# MINI_SAM_D51_r025_b001.net
KiCad netlist of a schematic drawn in EAGLE
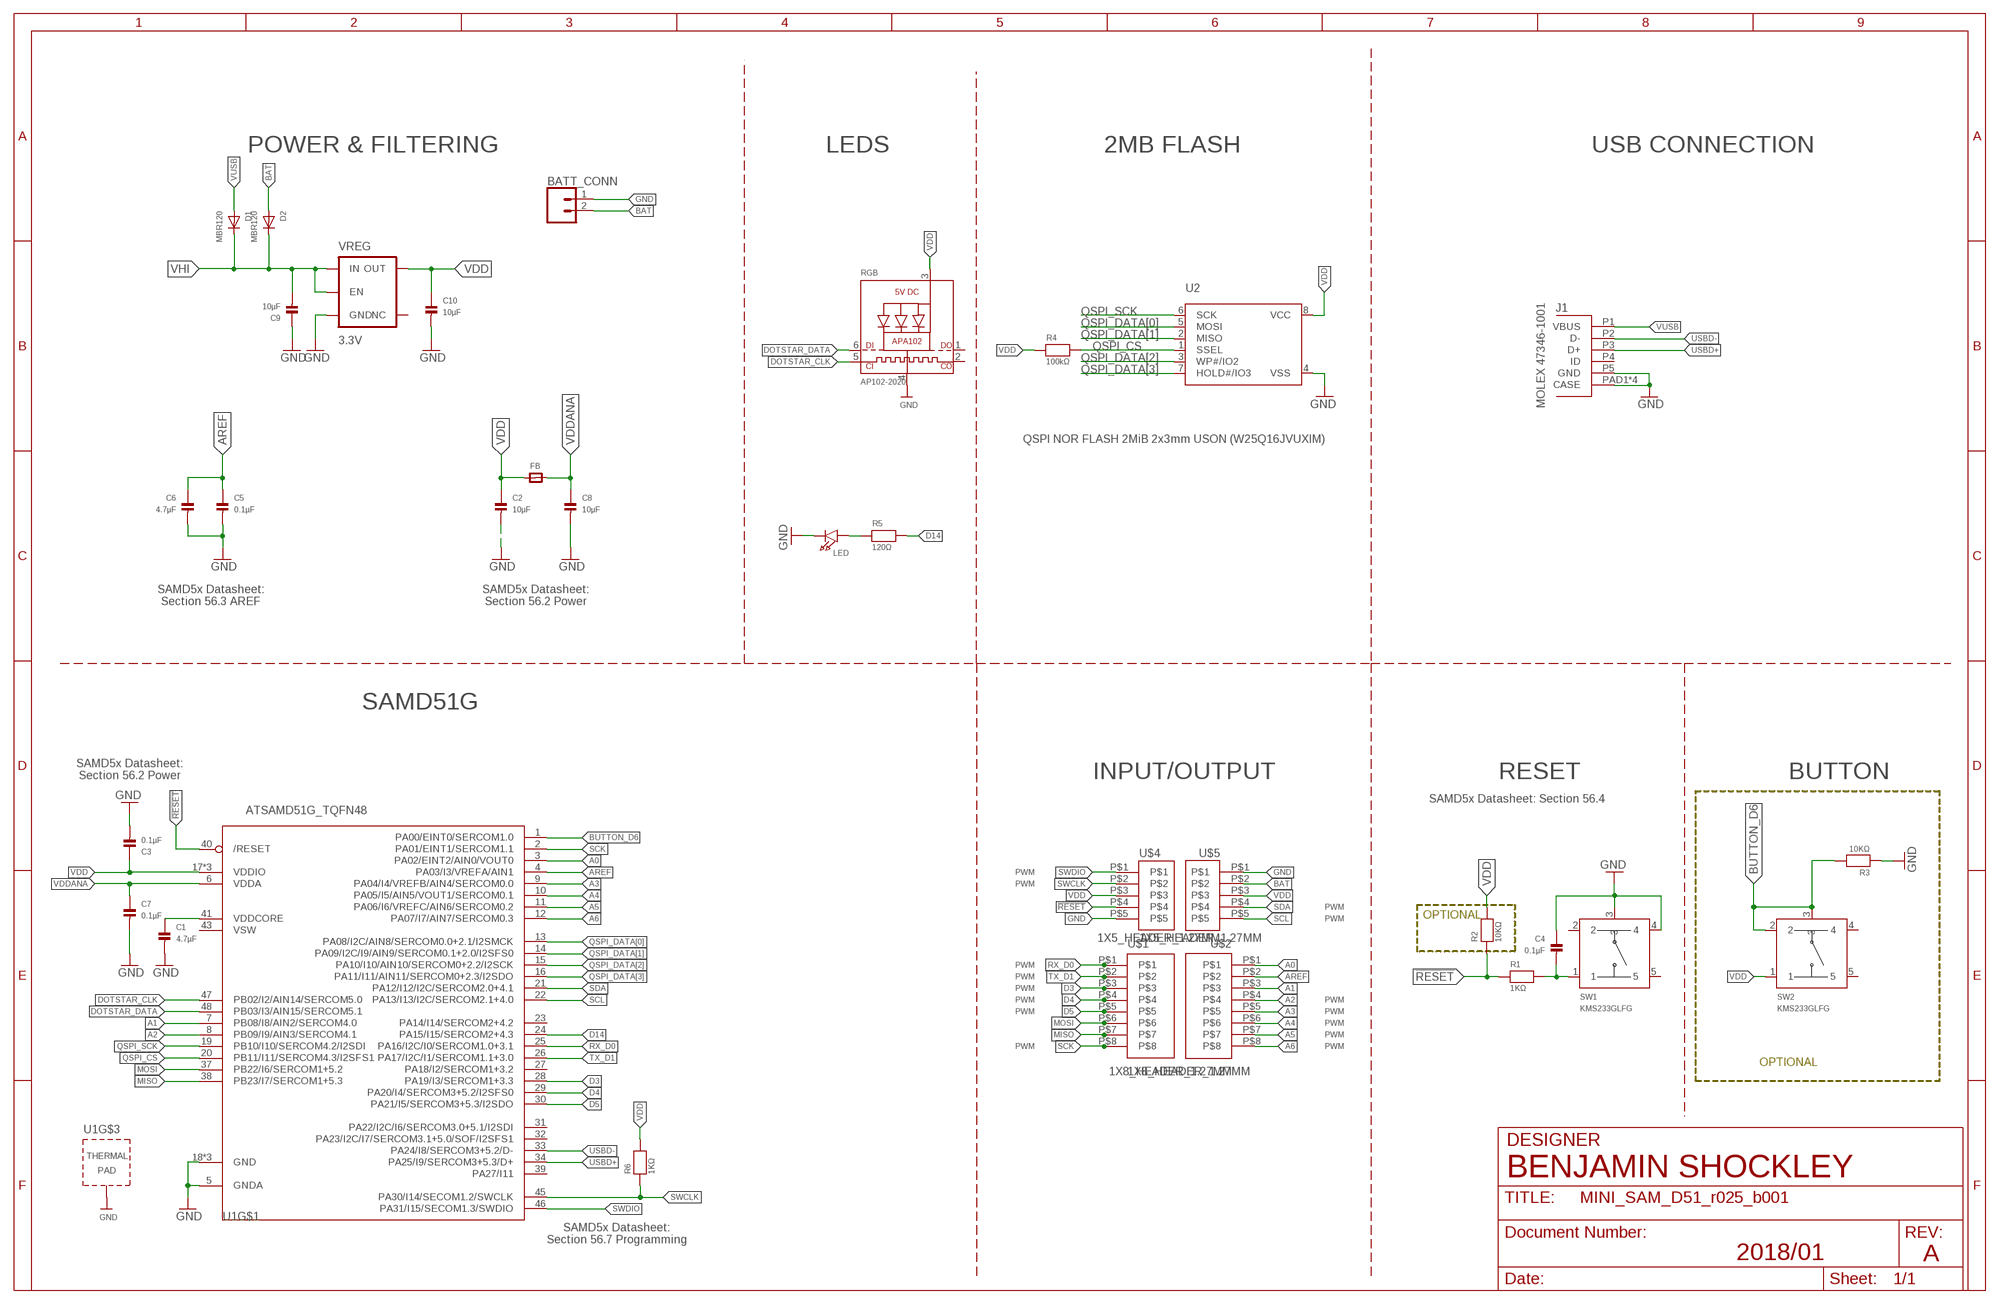
[diagram p0: schematic, sheet 1]

(export (version "E")
  (design (tool "Eeschema 10.0.6"))
  (components
    (comp (ref "BATT_CONN")
      (value "CONN_02-JST-2MM-SMT")
      (footprint "eagle-import:JST-2-SMD_NO_PASTE")
      (libsource (lib "eagle-import") (part "CONN_02-JST-2MM-SMT"))
    )
    (comp (ref "C1")
      (value "4.7µF")
      (footprint "eagle-import:0603_CAPACITOR")
      (libsource (lib "eagle-import") (part "CAP_CERAMICQUIRKY"))
    )
    (comp (ref "C2")
      (value "10µF")
      (footprint "eagle-import:0603_CAPACITOR")
      (libsource (lib "eagle-import") (part "CAP_CERAMICQUIRKY"))
    )
    (comp (ref "C3")
      (value "0.1µF")
      (footprint "eagle-import:0603_CAPACITOR")
      (libsource (lib "eagle-import") (part "CAP_CERAMICQUIRKY"))
    )
    (comp (ref "C4")
      (value "0.1µF")
      (footprint "eagle-import:0603_CAPACITOR")
      (libsource (lib "eagle-import") (part "CAP_CERAMICQUIRKY"))
    )
    (comp (ref "C5")
      (value "0.1µF")
      (footprint "eagle-import:0603_CAPACITOR")
      (libsource (lib "eagle-import") (part "CAP_CERAMICQUIRKY"))
    )
    (comp (ref "C6")
      (value "4.7µF")
      (footprint "eagle-import:0603_CAPACITOR")
      (libsource (lib "eagle-import") (part "CAP_CERAMICQUIRKY"))
    )
    (comp (ref "C7")
      (value "0.1µF")
      (footprint "eagle-import:0603_CAPACITOR")
      (libsource (lib "eagle-import") (part "CAP_CERAMICQUIRKY"))
    )
    (comp (ref "C8")
      (value "10µF")
      (footprint "eagle-import:0603_CAPACITOR")
      (libsource (lib "eagle-import") (part "CAP_CERAMICQUIRKY"))
    )
    (comp (ref "C9")
      (value "10µF")
      (footprint "eagle-import:0603_CAPACITOR")
      (libsource (lib "eagle-import") (part "CAP_CERAMICQUIRKY"))
    )
    (comp (ref "C10")
      (value "10µF")
      (footprint "eagle-import:0603_CAPACITOR")
      (libsource (lib "eagle-import") (part "CAP_CERAMICQUIRKY"))
    )
    (comp (ref "D1")
      (value "MBR120")
      (footprint "eagle-import:SOD-123FL")
      (libsource (lib "eagle-import") (part "DIODE_SOD-123FL"))
    )
    (comp (ref "D2")
      (value "MBR120")
      (footprint "eagle-import:SOD-123FL")
      (libsource (lib "eagle-import") (part "DIODE_SOD-123FL"))
    )
    (comp (ref "FB")
      (value "Impedence: 50 ohm @ 20 MHz, 220 Ohm @ 100 MHz; low DC resistance")
      (footprint "eagle-import:0603_INDUCTOR")
      (libsource (lib "eagle-import") (part "FERRITEQUIRKY"))
    )
    (comp (ref "J1")
      (value "MOLEX_47346-100147346")
      (footprint "eagle-import:MOLEX_47346-1001")
      (libsource (lib "eagle-import") (part "MOLEX_47346-100147346"))
    )
    (comp (ref "LED")
      (value "VLRK31Q1R2-GS08")
      (footprint "eagle-import:REVERSE_MOUNT_LED")
      (libsource (lib "eagle-import") (part "REVERSEMOUNTLED"))
    )
    (comp (ref "R1")
      (value "1KΩ")
      (footprint "eagle-import:0603_RESISTOR")
      (libsource (lib "eagle-import") (part "RESISTORQUIRKY"))
    )
    (comp (ref "R2")
      (value "10KΩ")
      (footprint "eagle-import:0603_RESISTOR")
      (libsource (lib "eagle-import") (part "RESISTORQUIRKY"))
    )
    (comp (ref "R3")
      (value "10KΩ")
      (footprint "eagle-import:0603_RESISTOR")
      (libsource (lib "eagle-import") (part "RESISTORQUIRKY"))
    )
    (comp (ref "R4")
      (value "100kΩ")
      (footprint "eagle-import:0603_RESISTOR")
      (libsource (lib "eagle-import") (part "RESISTORQUIRKY"))
    )
    (comp (ref "R5")
      (value "120Ω")
      (footprint "eagle-import:0603_RESISTOR")
      (libsource (lib "eagle-import") (part "RESISTORQUIRKY"))
    )
    (comp (ref "R6")
      (value "1KΩ")
      (footprint "eagle-import:0603_RESISTOR")
      (libsource (lib "eagle-import") (part "RESISTORQUIRKY"))
    )
    (comp (ref "RGB")
      (value "AP102-2020")
      (footprint "eagle-import:APA102_2020")
      (libsource (lib "eagle-import") (part "APA1022020"))
    )
    (comp (ref "SW1")
      (value "KMS233GLFG")
      (footprint "eagle-import:KMS_SWITCH")
      (libsource (lib "eagle-import") (part "KMS_SWITCHKMS"))
    )
    (comp (ref "SW2")
      (value "KMS233GLFG")
      (footprint "eagle-import:KMS_SWITCH")
      (libsource (lib "eagle-import") (part "KMS_SWITCHKMS"))
    )
    (comp (ref "U$1")
      (value "1X8_HEADER_1.27MM")
      (footprint "eagle-import:1X8_HEADER_1.27MM")
      (libsource (lib "eagle-import") (part "1X8_HEADER_1.27MM"))
    )
    (comp (ref "U$2")
      (value "1X8_HEADER_1.27MM")
      (footprint "eagle-import:1X8_HEADER_1.27MM")
      (libsource (lib "eagle-import") (part "1X8_HEADER_1.27MM"))
    )
    (comp (ref "U$4")
      (value "1X5_HEADER_1.27MM")
      (footprint "eagle-import:1X5_HEADER_1.27MM")
      (libsource (lib "eagle-import") (part "1X5_HEADER_1.27MM"))
    )
    (comp (ref "U$5")
      (value "1X5_HEADER_1.27MM")
      (footprint "eagle-import:1X5_HEADER_1.27MM")
      (libsource (lib "eagle-import") (part "1X5_HEADER_1.27MM"))
    )
    (comp (ref "U1")
      (value "ATSAMD51G_TQFN48")
      (footprint "eagle-import:TQFN48_7MM")
      (libsource (lib "eagle-import") (part "ATSAMD51G_TQFN48"))
    )
    (comp (ref "U2")
      (value "QSPI NOR FLASH 2MiB 2x3mm USON (W25Q16JVUXIM)")
      (footprint "eagle-import:USON8")
      (libsource (lib "eagle-import") (part "SPIFLASH_8PINUX"))
    )
    (comp (ref "VREG")
      (value "3.3V")
      (footprint "eagle-import:SOT23-5")
      (libsource (lib "eagle-import") (part "V_REG_AP2112K-3.3V"))
    )
  )
  (nets
    (net (code "1") (name "/VSW") (class "Default")
      (node (ref "U1") (pin "43") (pinfunction "VSW_43") (pintype "power_in"))
    )
    (net (code "2") (name "/~{RESET}") (class "Default")
      (node (ref "R1") (pin "1") (pinfunction "1_1") (pintype "passive"))
      (node (ref "R2") (pin "1") (pinfunction "1_1") (pintype "passive"))
      (node (ref "U$4") (pin "P$4") (pinfunction "P$4_P$4") (pintype "bidirectional"))
      (node (ref "U1") (pin "40") (pinfunction "/RESET_40") (pintype "bidirectional"))
    )
    (net (code "3") (name "A0") (class "Default")
      (node (ref "U$2") (pin "P$1") (pinfunction "P$1_P$1") (pintype "bidirectional"))
      (node (ref "U1") (pin "3") (pinfunction "PA02/EINT2/AIN0/VOUT0_3") (pintype "bidirectional"))
    )
    (net (code "4") (name "A1") (class "Default")
      (node (ref "U$2") (pin "P$3") (pinfunction "P$3_P$3") (pintype "bidirectional"))
      (node (ref "U1") (pin "7") (pinfunction "PB08/I8/AIN2/SERCOM4.0_7") (pintype "bidirectional"))
    )
    (net (code "5") (name "A2") (class "Default")
      (node (ref "U$2") (pin "P$4") (pinfunction "P$4_P$4") (pintype "bidirectional"))
      (node (ref "U1") (pin "8") (pinfunction "PB09/I9/AIN3/SERCOM4.1_8") (pintype "bidirectional"))
    )
    (net (code "6") (name "A3") (class "Default")
      (node (ref "U$2") (pin "P$5") (pinfunction "P$5_P$5") (pintype "bidirectional"))
      (node (ref "U1") (pin "9") (pinfunction "PA04/I4/VREFB/AIN4/SERCOM0.0_9") (pintype "bidirectional"))
    )
    (net (code "7") (name "A4") (class "Default")
      (node (ref "U$2") (pin "P$6") (pinfunction "P$6_P$6") (pintype "bidirectional"))
      (node (ref "U1") (pin "10") (pinfunction "PA05/I5/AIN5/VOUT1/SERCOM0.1_10") (pintype "bidirectional"))
    )
    (net (code "8") (name "A5") (class "Default")
      (node (ref "U$2") (pin "P$7") (pinfunction "P$7_P$7") (pintype "bidirectional"))
      (node (ref "U1") (pin "11") (pinfunction "PA06/I6/VREFC/AIN6/SERCOM0.2_11") (pintype "bidirectional"))
    )
    (net (code "9") (name "A6") (class "Default")
      (node (ref "U$2") (pin "P$8") (pinfunction "P$8_P$8") (pintype "bidirectional"))
      (node (ref "U1") (pin "12") (pinfunction "PA07/I7/AIN7/SERCOM0.3_12") (pintype "bidirectional"))
    )
    (net (code "10") (name "AREF") (class "Default")
      (node (ref "C5") (pin "1") (pinfunction "P$1_1") (pintype "passive"))
      (node (ref "C6") (pin "1") (pinfunction "P$1_1") (pintype "passive"))
      (node (ref "U$2") (pin "P$2") (pinfunction "P$2_P$2") (pintype "bidirectional"))
      (node (ref "U1") (pin "4") (pinfunction "PA03/I3/VREFA/AIN1_4") (pintype "bidirectional"))
    )
    (net (code "11") (name "BAT") (class "Default")
      (node (ref "BATT_CONN") (pin "2") (pinfunction "1_2") (pintype "passive"))
      (node (ref "D2") (pin "A") (pinfunction "A_A") (pintype "passive"))
      (node (ref "U$5") (pin "P$2") (pinfunction "P$2_P$2") (pintype "bidirectional"))
    )
    (net (code "12") (name "BUTTON_D6") (class "Default")
      (node (ref "R3") (pin "2") (pinfunction "2_2") (pintype "passive"))
      (node (ref "SW2") (pin "2") (pinfunction "2_2") (pintype "bidirectional"))
      (node (ref "SW2") (pin "3") (pinfunction "3_3") (pintype "bidirectional"))
      (node (ref "U1") (pin "1") (pinfunction "PA00/EINT0/SERCOM1.0_1") (pintype "bidirectional"))
    )
    (net (code "13") (name "D3") (class "Default")
      (node (ref "U$1") (pin "P$3") (pinfunction "P$3_P$3") (pintype "bidirectional"))
      (node (ref "U1") (pin "28") (pinfunction "PA19/I3/SERCOM1+3.3_28") (pintype "bidirectional"))
    )
    (net (code "14") (name "D4") (class "Default")
      (node (ref "U$1") (pin "P$4") (pinfunction "P$4_P$4") (pintype "bidirectional"))
      (node (ref "U1") (pin "29") (pinfunction "PA20/I4/SERCOM3+5.2/I2SFS0_29") (pintype "bidirectional"))
    )
    (net (code "15") (name "D5") (class "Default")
      (node (ref "U$1") (pin "P$5") (pinfunction "P$5_P$5") (pintype "bidirectional"))
      (node (ref "U1") (pin "30") (pinfunction "PA21/I5/SERCOM3+5.3/I2SDO_30") (pintype "bidirectional"))
    )
    (net (code "16") (name "D14") (class "Default")
      (node (ref "R5") (pin "2") (pinfunction "2_2") (pintype "passive"))
      (node (ref "U1") (pin "24") (pinfunction "PA15/I15/SERCOM2+4.3_24") (pintype "bidirectional"))
    )
    (net (code "17") (name "DOTSTAR_CLK") (class "Default")
      (node (ref "RGB") (pin "5") (pinfunction "CKI_5") (pintype "input"))
      (node (ref "U1") (pin "47") (pinfunction "PB02/I2/AIN14/SERCOM5.0_47") (pintype "bidirectional"))
    )
    (net (code "18") (name "DOTSTAR_DATA") (class "Default")
      (node (ref "RGB") (pin "6") (pinfunction "DI_6") (pintype "input"))
      (node (ref "U1") (pin "48") (pinfunction "PB03/I3/AIN15/SERCOM5.1_48") (pintype "bidirectional"))
    )
    (net (code "19") (name "GND") (class "Default")
      (node (ref "BATT_CONN") (pin "1") (pinfunction "2_1") (pintype "passive"))
      (node (ref "C1") (pin "2") (pinfunction "P$2_2") (pintype "passive"))
      (node (ref "C10") (pin "2") (pinfunction "P$2_2") (pintype "passive"))
      (node (ref "C2") (pin "2") (pinfunction "P$2_2") (pintype "passive"))
      (node (ref "C3") (pin "2") (pinfunction "P$2_2") (pintype "passive"))
      (node (ref "C4") (pin "1") (pinfunction "P$1_1") (pintype "passive"))
      (node (ref "C5") (pin "2") (pinfunction "P$2_2") (pintype "passive"))
      (node (ref "C6") (pin "2") (pinfunction "P$2_2") (pintype "passive"))
      (node (ref "C7") (pin "2") (pinfunction "P$2_2") (pintype "passive"))
      (node (ref "C8") (pin "2") (pinfunction "P$2_2") (pintype "passive"))
      (node (ref "C9") (pin "1") (pinfunction "P$1_1") (pintype "passive"))
      (node (ref "J1") (pin "P5") (pinfunction "GND_P5") (pintype "power_in"))
      (node (ref "J1") (pin "PAD1") (pinfunction "CASE_PAD1") (pintype "bidirectional"))
      (node (ref "J1") (pin "PAD2") (pinfunction "CASE_PAD2") (pintype "bidirectional"))
      (node (ref "J1") (pin "PAD3") (pinfunction "CASE_PAD3") (pintype "bidirectional"))
      (node (ref "J1") (pin "PAD4") (pinfunction "CASE_PAD4") (pintype "bidirectional"))
      (node (ref "LED") (pin "C") (pinfunction "C_C") (pintype "passive"))
      (node (ref "R3") (pin "1") (pinfunction "1_1") (pintype "passive"))
      (node (ref "RGB") (pin "4") (pinfunction "GND_4") (pintype "power_in"))
      (node (ref "SW1") (pin "3") (pinfunction "3_3") (pintype "bidirectional"))
      (node (ref "SW1") (pin "4") (pinfunction "4_4") (pintype "bidirectional"))
      (node (ref "U$4") (pin "P$5") (pinfunction "P$5_P$5") (pintype "bidirectional"))
      (node (ref "U$5") (pin "P$1") (pinfunction "P$1_P$1") (pintype "bidirectional"))
      (node (ref "U1") (pin "18") (pinfunction "GND_18") (pintype "power_in"))
      (node (ref "U1") (pin "35") (pinfunction "GND_35") (pintype "power_in"))
      (node (ref "U1") (pin "42") (pinfunction "GND_42") (pintype "power_in"))
      (node (ref "U1") (pin "5") (pinfunction "GNDA_5") (pintype "power_in"))
      (node (ref "U1") (pin "THERMAL") (pinfunction "TP_THERMAL") (pintype "power_in"))
      (node (ref "U2") (pin "4") (pinfunction "VSS_4") (pintype "bidirectional"))
      (node (ref "VREG") (pin "2") (pinfunction "GND_2") (pintype "input"))
    )
    (net (code "20") (name "MISO") (class "Default")
      (node (ref "U$1") (pin "P$7") (pinfunction "P$7_P$7") (pintype "bidirectional"))
      (node (ref "U1") (pin "38") (pinfunction "PB23/I7/SERCOM1+5.3_38") (pintype "bidirectional"))
    )
    (net (code "21") (name "MOSI") (class "Default")
      (node (ref "U$1") (pin "P$6") (pinfunction "P$6_P$6") (pintype "bidirectional"))
      (node (ref "U1") (pin "37") (pinfunction "PB22/I6/SERCOM1+5.2_37") (pintype "bidirectional"))
    )
    (net (code "22") (name "Net-(C1-P$1)") (class "Default")
      (node (ref "C1") (pin "1") (pinfunction "P$1_1") (pintype "passive"))
      (node (ref "U1") (pin "41") (pinfunction "VDDCORE_41") (pintype "power_in"))
    )
    (net (code "23") (name "Net-(C4-P$2)") (class "Default")
      (node (ref "C4") (pin "2") (pinfunction "P$2_2") (pintype "passive"))
      (node (ref "R1") (pin "2") (pinfunction "2_2") (pintype "passive"))
      (node (ref "SW1") (pin "1") (pinfunction "1_1") (pintype "bidirectional"))
    )
    (net (code "24") (name "Net-(LED-PadA)") (class "Default")
      (node (ref "LED") (pin "A") (pinfunction "A_A") (pintype "passive"))
      (node (ref "R5") (pin "1") (pinfunction "1_1") (pintype "passive"))
    )
    (net (code "25") (name "QSPI_CS") (class "Default")
      (node (ref "R4") (pin "2") (pinfunction "2_2") (pintype "passive"))
      (node (ref "U1") (pin "20") (pinfunction "PB11/I11/SERCOM4.3/I2SFS1_20") (pintype "bidirectional"))
      (node (ref "U2") (pin "1") (pinfunction "SSEL_1") (pintype "bidirectional"))
    )
    (net (code "26") (name "QSPI_DATA[0]") (class "Default")
      (node (ref "U1") (pin "13") (pinfunction "PA08/I2C/AIN8/SERCOM0.0+2.1/I2SMCK_13") (pintype "bidirectional"))
      (node (ref "U2") (pin "5") (pinfunction "MOSI_5") (pintype "bidirectional"))
    )
    (net (code "27") (name "QSPI_DATA[1]") (class "Default")
      (node (ref "U1") (pin "14") (pinfunction "PA09/I2C/I9/AIN9/SERCOM0.1+2.0/I2SFS0_14") (pintype "bidirectional"))
      (node (ref "U2") (pin "2") (pinfunction "MISO_2") (pintype "bidirectional"))
    )
    (net (code "28") (name "QSPI_DATA[2]") (class "Default")
      (node (ref "U1") (pin "15") (pinfunction "PA10/I10/AIN10/SERCOM0+2.2/I2SCK_15") (pintype "bidirectional"))
      (node (ref "U2") (pin "3") (pinfunction "WP#/IO2_3") (pintype "bidirectional"))
    )
    (net (code "29") (name "QSPI_DATA[3]") (class "Default")
      (node (ref "U1") (pin "16") (pinfunction "PA11/I11/AIN11/SERCOM0+2.3/I2SDO_16") (pintype "bidirectional"))
      (node (ref "U2") (pin "7") (pinfunction "HOLD#/IO3_7") (pintype "bidirectional"))
    )
    (net (code "30") (name "QSPI_SCK") (class "Default")
      (node (ref "U1") (pin "19") (pinfunction "PB10/I10/SERCOM4.2/I2SDI_19") (pintype "bidirectional"))
      (node (ref "U2") (pin "6") (pinfunction "SCK_6") (pintype "bidirectional"))
    )
    (net (code "31") (name "RX_D0") (class "Default")
      (node (ref "U$1") (pin "P$1") (pinfunction "P$1_P$1") (pintype "bidirectional"))
      (node (ref "U1") (pin "25") (pinfunction "PA16/I2C/I0/SERCOM1.0+3.1_25") (pintype "bidirectional"))
    )
    (net (code "32") (name "SCK") (class "Default")
      (node (ref "U$1") (pin "P$8") (pinfunction "P$8_P$8") (pintype "bidirectional"))
      (node (ref "U1") (pin "2") (pinfunction "PA01/EINT1/SERCOM1.1_2") (pintype "bidirectional"))
    )
    (net (code "33") (name "SCL") (class "Default")
      (node (ref "U$5") (pin "P$5") (pinfunction "P$5_P$5") (pintype "bidirectional"))
      (node (ref "U1") (pin "22") (pinfunction "PA13/I13/I2C/SERCOM2.1+4.0_22") (pintype "bidirectional"))
    )
    (net (code "34") (name "SDA") (class "Default")
      (node (ref "U$5") (pin "P$4") (pinfunction "P$4_P$4") (pintype "bidirectional"))
      (node (ref "U1") (pin "21") (pinfunction "PA12/I12/I2C/SERCOM2.0+4.1_21") (pintype "bidirectional"))
    )
    (net (code "35") (name "SWCLK") (class "Default")
      (node (ref "R6") (pin "1") (pinfunction "1_1") (pintype "passive"))
      (node (ref "U$4") (pin "P$2") (pinfunction "P$2_P$2") (pintype "bidirectional"))
      (node (ref "U1") (pin "45") (pinfunction "PA30/I14/SECOM1.2/SWCLK_45") (pintype "bidirectional"))
    )
    (net (code "36") (name "SWDIO") (class "Default")
      (node (ref "U$4") (pin "P$1") (pinfunction "P$1_P$1") (pintype "bidirectional"))
      (node (ref "U1") (pin "46") (pinfunction "PA31/I15/SECOM1.3/SWDIO_46") (pintype "bidirectional"))
    )
    (net (code "37") (name "TX_D1") (class "Default")
      (node (ref "U$1") (pin "P$2") (pinfunction "P$2_P$2") (pintype "bidirectional"))
      (node (ref "U1") (pin "26") (pinfunction "PA17/I2C/I1/SERCOM1.1+3.0_26") (pintype "bidirectional"))
    )
    (net (code "38") (name "USBD+") (class "Default")
      (node (ref "J1") (pin "P3") (pinfunction "D+_P3") (pintype "bidirectional"))
      (node (ref "U1") (pin "34") (pinfunction "PA25/I9/SERCOM3+5.3/D+_34") (pintype "bidirectional"))
    )
    (net (code "39") (name "USBD-") (class "Default")
      (node (ref "J1") (pin "P2") (pinfunction "D-_P2") (pintype "bidirectional"))
      (node (ref "U1") (pin "33") (pinfunction "PA24/I8/SERCOM3+5.2/D-_33") (pintype "bidirectional"))
    )
    (net (code "40") (name "VDD") (class "Default")
      (node (ref "C10") (pin "1") (pinfunction "P$1_1") (pintype "passive"))
      (node (ref "C2") (pin "1") (pinfunction "P$1_1") (pintype "passive"))
      (node (ref "C3") (pin "1") (pinfunction "P$1_1") (pintype "passive"))
      (node (ref "FB") (pin "1") (pinfunction "P$1_1") (pintype "passive"))
      (node (ref "R2") (pin "2") (pinfunction "2_2") (pintype "passive"))
      (node (ref "R4") (pin "1") (pinfunction "1_1") (pintype "passive"))
      (node (ref "R6") (pin "2") (pinfunction "2_2") (pintype "passive"))
      (node (ref "RGB") (pin "3") (pinfunction "VDD_3") (pintype "power_in"))
      (node (ref "SW2") (pin "1") (pinfunction "1_1") (pintype "bidirectional"))
      (node (ref "U$4") (pin "P$3") (pinfunction "P$3_P$3") (pintype "bidirectional"))
      (node (ref "U$5") (pin "P$3") (pinfunction "P$3_P$3") (pintype "bidirectional"))
      (node (ref "U1") (pin "17") (pinfunction "VDDIO_17") (pintype "power_in"))
      (node (ref "U1") (pin "36") (pinfunction "VDDIO_36") (pintype "power_in"))
      (node (ref "U1") (pin "44") (pinfunction "VDDIO_44") (pintype "power_in"))
      (node (ref "U2") (pin "8") (pinfunction "VCC_8") (pintype "bidirectional"))
      (node (ref "VREG") (pin "5") (pinfunction "OUT_5") (pintype "passive"))
    )
    (net (code "41") (name "VDDANA") (class "Default")
      (node (ref "C7") (pin "1") (pinfunction "P$1_1") (pintype "passive"))
      (node (ref "C8") (pin "1") (pinfunction "P$1_1") (pintype "passive"))
      (node (ref "FB") (pin "2") (pinfunction "P$2_2") (pintype "passive"))
      (node (ref "U1") (pin "6") (pinfunction "VDDA_6") (pintype "power_in"))
    )
    (net (code "42") (name "VHI") (class "Default")
      (node (ref "C9") (pin "2") (pinfunction "P$2_2") (pintype "passive"))
      (node (ref "D1") (pin "C") (pinfunction "C_C") (pintype "passive"))
      (node (ref "D2") (pin "C") (pinfunction "C_C") (pintype "passive"))
      (node (ref "VREG") (pin "1") (pinfunction "IN_1") (pintype "input"))
      (node (ref "VREG") (pin "3") (pinfunction "EN_3") (pintype "input"))
    )
    (net (code "43") (name "VUSB") (class "Default")
      (node (ref "D1") (pin "A") (pinfunction "A_A") (pintype "passive"))
      (node (ref "J1") (pin "P1") (pinfunction "VBUS_P1") (pintype "power_in"))
    )
    (net (code "44") (name "unconnected-(J1-ID-PadP4)") (class "Default")
      (node (ref "J1") (pin "P4") (pinfunction "ID_P4") (pintype "bidirectional"))
    )
    (net (code "45") (name "unconnected-(RGB-CKO-Pad2)") (class "Default")
      (node (ref "RGB") (pin "2") (pinfunction "CKO_2") (pintype "output"))
    )
    (net (code "46") (name "unconnected-(RGB-DO-Pad1)") (class "Default")
      (node (ref "RGB") (pin "1") (pinfunction "DO_1") (pintype "output"))
    )
    (net (code "47") (name "unconnected-(SW1-Pad2)") (class "Default")
      (node (ref "SW1") (pin "2") (pinfunction "2_2") (pintype "bidirectional"))
    )
    (net (code "48") (name "unconnected-(SW1-Pad5)") (class "Default")
      (node (ref "SW1") (pin "5") (pinfunction "5_5") (pintype "bidirectional"))
    )
    (net (code "49") (name "unconnected-(SW2-Pad4)") (class "Default")
      (node (ref "SW2") (pin "4") (pinfunction "4_4") (pintype "bidirectional"))
    )
    (net (code "50") (name "unconnected-(SW2-Pad5)") (class "Default")
      (node (ref "SW2") (pin "5") (pinfunction "5_5") (pintype "bidirectional"))
    )
    (net (code "51") (name "unconnected-(U1A-PA14{slash}I14{slash}SERCOM2+4.2-Pad23)") (class "Default")
      (node (ref "U1") (pin "23") (pinfunction "PA14/I14/SERCOM2+4.2_23") (pintype "bidirectional"))
    )
    (net (code "52") (name "unconnected-(U1A-PA18{slash}I2{slash}SERCOM1+3.2-Pad27)") (class "Default")
      (node (ref "U1") (pin "27") (pinfunction "PA18/I2/SERCOM1+3.2_27") (pintype "bidirectional"))
    )
    (net (code "53") (name "unconnected-(U1A-PA22{slash}I2C{slash}I6{slash}SERCOM3.0+5.1{slash}I2SDI-Pad31)") (class "Default")
      (node (ref "U1") (pin "31") (pinfunction "PA22/I2C/I6/SERCOM3.0+5.1/I2SDI_31") (pintype "bidirectional"))
    )
    (net (code "54") (name "unconnected-(U1A-PA23{slash}I2C{slash}I7{slash}SERCOM3.1+5.0{slash}SOF{slash}I2SFS1-Pad32)") (class "Default")
      (node (ref "U1") (pin "32") (pinfunction "PA23/I2C/I7/SERCOM3.1+5.0/SOF/I2SFS1_32") (pintype "bidirectional"))
    )
    (net (code "55") (name "unconnected-(U1A-PA27{slash}I11-Pad39)") (class "Default")
      (node (ref "U1") (pin "39") (pinfunction "PA27/I11_39") (pintype "bidirectional"))
    )
    (net (code "56") (name "unconnected-(VREG-NC-Pad4)") (class "Default")
      (node (ref "VREG") (pin "4") (pinfunction "NC_4") (pintype "input"))
    )
  )
)
